# open-bldc-power.net
KiCad netlist of a schematic drawn in EAGLE
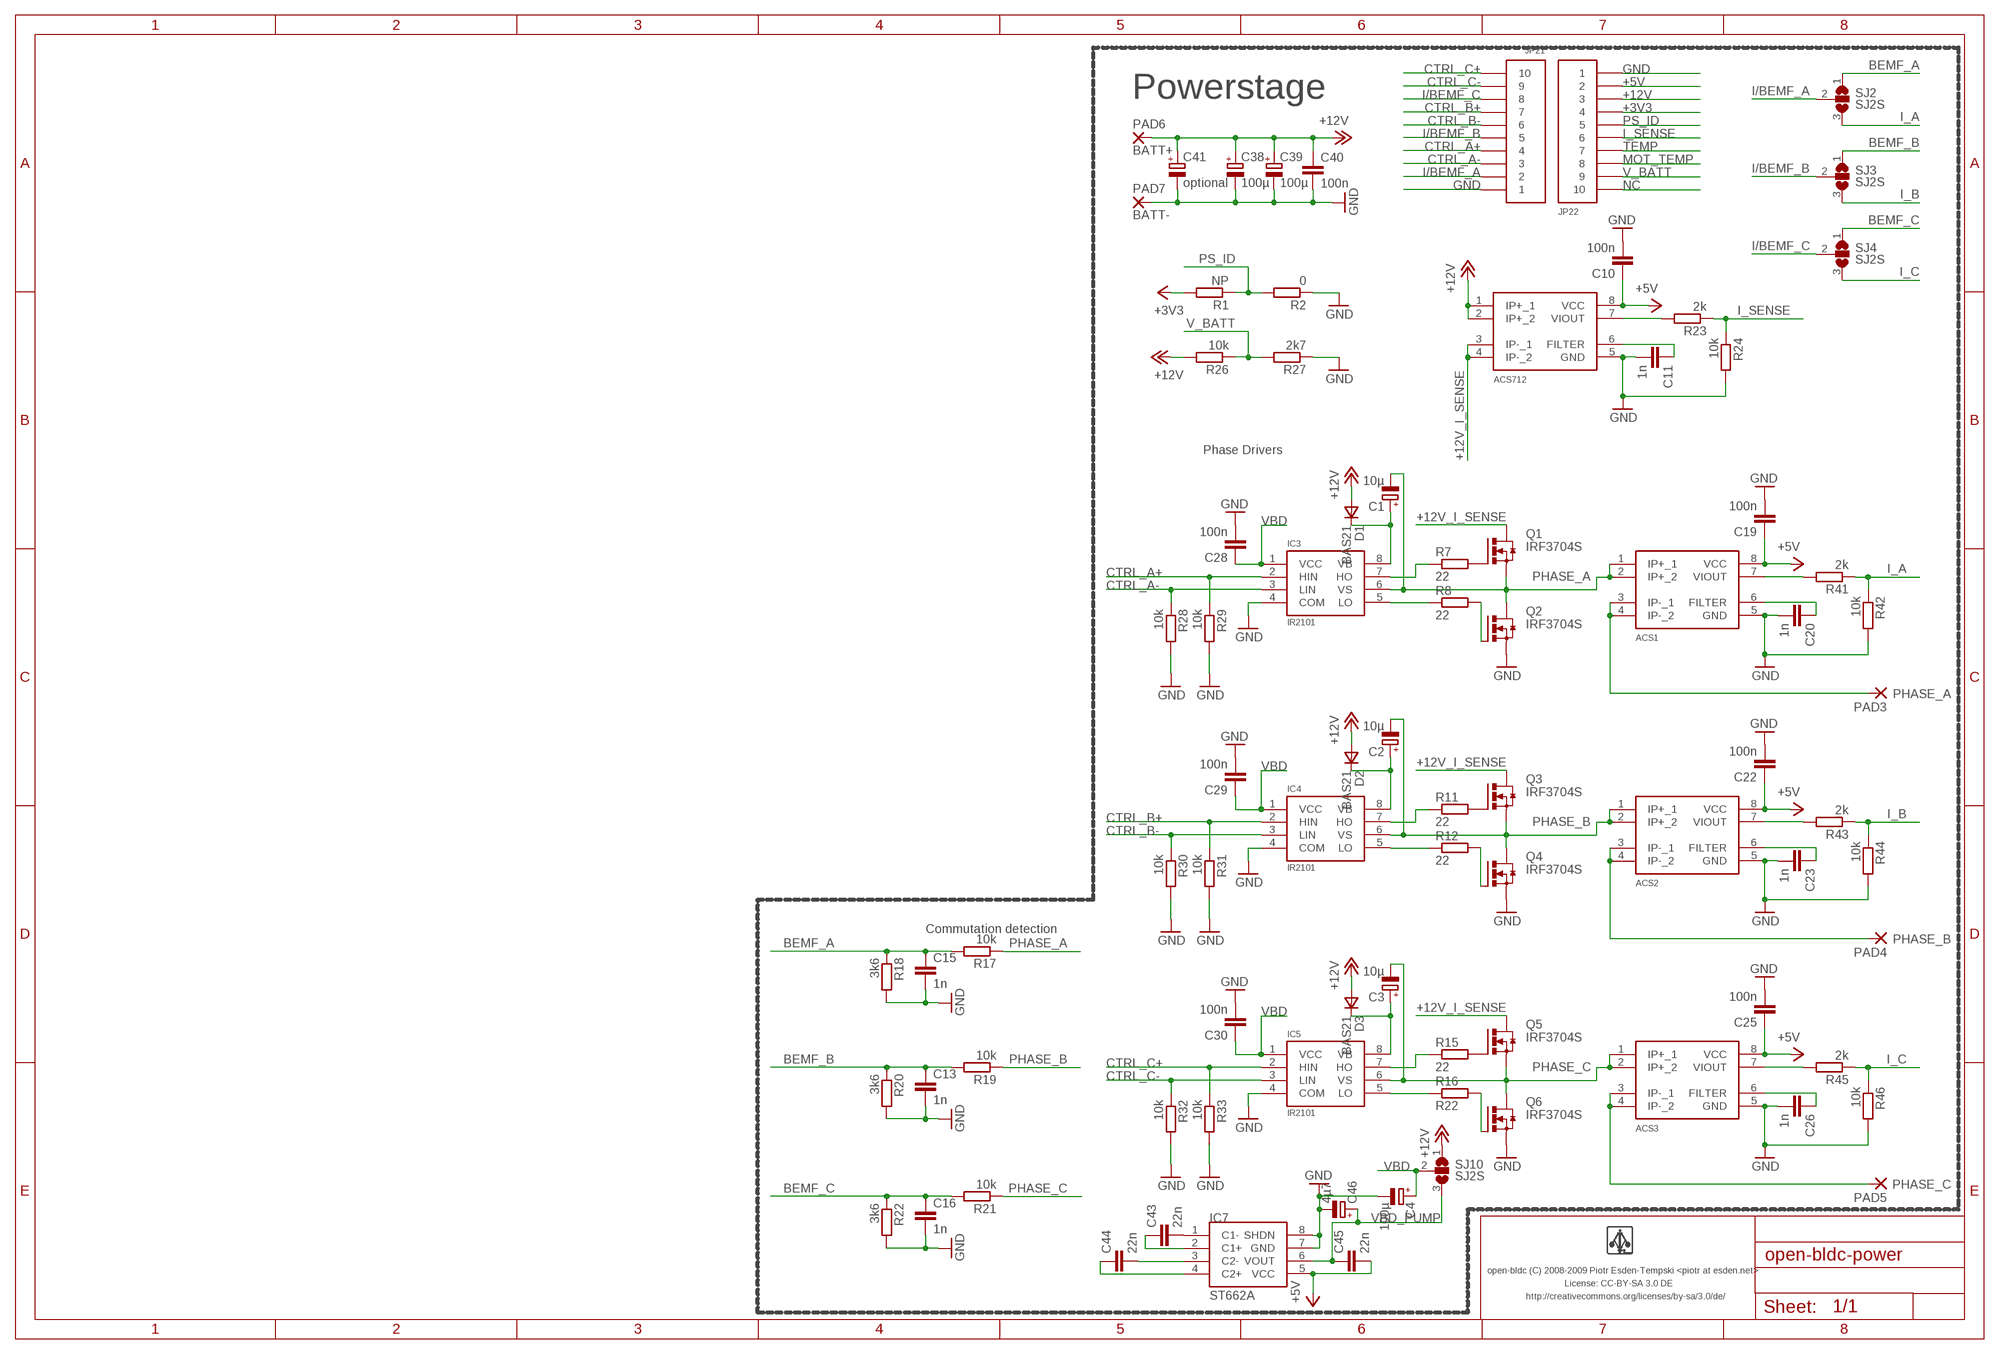
[diagram p0: schematic, sheet 1]

(export (version "E")
  (design (tool "Eeschema 10.0.6"))
  (components
    (comp (ref "ACS1")
      (value "ACS712")
      (footprint "eagle-import:SO8")
      (libsource (lib "eagle-import") (part "ACS712"))
    )
    (comp (ref "ACS2")
      (value "ACS712")
      (footprint "eagle-import:SO8")
      (libsource (lib "eagle-import") (part "ACS712"))
    )
    (comp (ref "ACS3")
      (value "ACS712")
      (footprint "eagle-import:SO8")
      (libsource (lib "eagle-import") (part "ACS712"))
    )
    (comp (ref "ACS712")
      (value "ACS712")
      (footprint "eagle-import:SO8")
      (libsource (lib "eagle-import") (part "ACS712"))
    )
    (comp (ref "C1")
      (value "10µ")
      (footprint "eagle-import:A_3216-18R")
      (libsource (lib "eagle-import") (part "CPOL-EUA/3216-18R"))
    )
    (comp (ref "C2")
      (value "10µ")
      (footprint "eagle-import:A_3216-18R")
      (libsource (lib "eagle-import") (part "CPOL-EUA/3216-18R"))
    )
    (comp (ref "C3")
      (value "10µ")
      (footprint "eagle-import:A_3216-18R")
      (libsource (lib "eagle-import") (part "CPOL-EUA/3216-18R"))
    )
    (comp (ref "C4")
      (value "100µ")
      (footprint "eagle-import:D_7343-31R")
      (libsource (lib "eagle-import") (part "CPOL-EUD/7343-31R"))
    )
    (comp (ref "C10")
      (value "100n")
      (footprint "eagle-import:C0603")
      (libsource (lib "eagle-import") (part "C-EUC0603"))
    )
    (comp (ref "C11")
      (value "1n")
      (footprint "eagle-import:C0603")
      (libsource (lib "eagle-import") (part "C-EUC0603"))
    )
    (comp (ref "C13")
      (value "1n")
      (footprint "eagle-import:C0603")
      (libsource (lib "eagle-import") (part "C-EUC0603"))
    )
    (comp (ref "C15")
      (value "1n")
      (footprint "eagle-import:C0603")
      (libsource (lib "eagle-import") (part "C-EUC0603"))
    )
    (comp (ref "C16")
      (value "1n")
      (footprint "eagle-import:C0603")
      (libsource (lib "eagle-import") (part "C-EUC0603"))
    )
    (comp (ref "C19")
      (value "100n")
      (footprint "eagle-import:C0603")
      (libsource (lib "eagle-import") (part "C-EUC0603"))
    )
    (comp (ref "C20")
      (value "1n")
      (footprint "eagle-import:C0603")
      (libsource (lib "eagle-import") (part "C-EUC0603"))
    )
    (comp (ref "C22")
      (value "100n")
      (footprint "eagle-import:C0603")
      (libsource (lib "eagle-import") (part "C-EUC0603"))
    )
    (comp (ref "C23")
      (value "1n")
      (footprint "eagle-import:C0603")
      (libsource (lib "eagle-import") (part "C-EUC0603"))
    )
    (comp (ref "C25")
      (value "100n")
      (footprint "eagle-import:C0603")
      (libsource (lib "eagle-import") (part "C-EUC0603"))
    )
    (comp (ref "C26")
      (value "1n")
      (footprint "eagle-import:C0603")
      (libsource (lib "eagle-import") (part "C-EUC0603"))
    )
    (comp (ref "C28")
      (value "100n")
      (footprint "eagle-import:C0603")
      (libsource (lib "eagle-import") (part "C-EUC0603"))
    )
    (comp (ref "C29")
      (value "100n")
      (footprint "eagle-import:C0603")
      (libsource (lib "eagle-import") (part "C-EUC0603"))
    )
    (comp (ref "C30")
      (value "100n")
      (footprint "eagle-import:C0603")
      (libsource (lib "eagle-import") (part "C-EUC0603"))
    )
    (comp (ref "C38")
      (value "100µ")
      (footprint "eagle-import:D_7343-31R")
      (libsource (lib "eagle-import") (part "CPOL-EUD/7343-31R"))
    )
    (comp (ref "C39")
      (value "100µ")
      (footprint "eagle-import:D_7343-31R")
      (libsource (lib "eagle-import") (part "CPOL-EUD/7343-31R"))
    )
    (comp (ref "C40")
      (value "100n")
      (footprint "eagle-import:C0603")
      (libsource (lib "eagle-import") (part "C-EUC0603"))
    )
    (comp (ref "C41")
      (value "optional")
      (footprint "eagle-import:E5-6")
      (libsource (lib "eagle-import") (part "CPOL-EUE5-6"))
    )
    (comp (ref "C43")
      (value "22n")
      (footprint "eagle-import:C0603")
      (libsource (lib "eagle-import") (part "C-EUC0603"))
    )
    (comp (ref "C44")
      (value "22n")
      (footprint "eagle-import:C0603")
      (libsource (lib "eagle-import") (part "C-EUC0603"))
    )
    (comp (ref "C45")
      (value "22n")
      (footprint "eagle-import:C0603")
      (libsource (lib "eagle-import") (part "C-EUC0603"))
    )
    (comp (ref "C46")
      (value "4µ7")
      (footprint "eagle-import:A_3216-18R")
      (libsource (lib "eagle-import") (part "CPOL-EUA/3216-18R"))
    )
    (comp (ref "D1")
      (value "BAS21")
      (footprint "eagle-import:SOT-23")
      (libsource (lib "eagle-import") (part "VAR2SOT23"))
    )
    (comp (ref "D2")
      (value "BAS21")
      (footprint "eagle-import:SOT-23")
      (libsource (lib "eagle-import") (part "VAR2SOT23"))
    )
    (comp (ref "D3")
      (value "BAS21")
      (footprint "eagle-import:SOT-23")
      (libsource (lib "eagle-import") (part "VAR2SOT23"))
    )
    (comp (ref "IC3")
      (value "IR2101")
      (footprint "eagle-import:SO-8")
      (libsource (lib "eagle-import") (part "IR2101"))
    )
    (comp (ref "IC4")
      (value "IR2101")
      (footprint "eagle-import:SO-8")
      (libsource (lib "eagle-import") (part "IR2101"))
    )
    (comp (ref "IC5")
      (value "IR2101")
      (footprint "eagle-import:SO-8")
      (libsource (lib "eagle-import") (part "IR2101"))
    )
    (comp (ref "IC7")
      (value "ST662A")
      (footprint "eagle-import:SO8")
      (libsource (lib "eagle-import") (part "ST662A"))
    )
    (comp (ref "JP21")
      (value "PIN_HDR_1.27MM_10")
      (footprint "eagle-import:PIN_HDR_1.27MM_10")
      (libsource (lib "eagle-import") (part "PIN_HDR_1.27MM_10_TH"))
    )
    (comp (ref "JP22")
      (value "PIN_HDR_1.27MM_10")
      (footprint "eagle-import:PIN_HDR_1.27MM_10")
      (libsource (lib "eagle-import") (part "PIN_HDR_1.27MM_10_TH"))
    )
    (comp (ref "PAD3")
      (value "PHASE_A")
      (footprint "eagle-import:SMD2,54-5,08")
      (libsource (lib "eagle-import") (part "SMD5"))
    )
    (comp (ref "PAD4")
      (value "PHASE_B")
      (footprint "eagle-import:SMD2,54-5,08")
      (libsource (lib "eagle-import") (part "SMD5"))
    )
    (comp (ref "PAD5")
      (value "PHASE_C")
      (footprint "eagle-import:SMD2,54-5,08")
      (libsource (lib "eagle-import") (part "SMD5"))
    )
    (comp (ref "PAD6")
      (value "BATT+")
      (footprint "eagle-import:SMD2,54-5,08")
      (libsource (lib "eagle-import") (part "SMD5"))
    )
    (comp (ref "PAD7")
      (value "BATT-")
      (footprint "eagle-import:SMD2,54-5,08")
      (libsource (lib "eagle-import") (part "SMD5"))
    )
    (comp (ref "Q1")
      (value "IRF3704S")
      (footprint "eagle-import:D2PACK")
      (libsource (lib "eagle-import") (part "IRF3704S"))
    )
    (comp (ref "Q2")
      (value "IRF3704S")
      (footprint "eagle-import:D2PACK")
      (libsource (lib "eagle-import") (part "IRF3704S"))
    )
    (comp (ref "Q3")
      (value "IRF3704S")
      (footprint "eagle-import:D2PACK")
      (libsource (lib "eagle-import") (part "IRF3704S"))
    )
    (comp (ref "Q4")
      (value "IRF3704S")
      (footprint "eagle-import:D2PACK")
      (libsource (lib "eagle-import") (part "IRF3704S"))
    )
    (comp (ref "Q5")
      (value "IRF3704S")
      (footprint "eagle-import:D2PACK")
      (libsource (lib "eagle-import") (part "IRF3704S"))
    )
    (comp (ref "Q6")
      (value "IRF3704S")
      (footprint "eagle-import:D2PACK")
      (libsource (lib "eagle-import") (part "IRF3704S"))
    )
    (comp (ref "R1")
      (value "NP")
      (footprint "eagle-import:R0603")
      (libsource (lib "eagle-import") (part "R-EU_R0603"))
    )
    (comp (ref "R2")
      (value "0")
      (footprint "eagle-import:R0603")
      (libsource (lib "eagle-import") (part "R-EU_R0603"))
    )
    (comp (ref "R7")
      (value "22")
      (footprint "eagle-import:R0603")
      (libsource (lib "eagle-import") (part "R-EU_R0603"))
    )
    (comp (ref "R8")
      (value "22")
      (footprint "eagle-import:R0603")
      (libsource (lib "eagle-import") (part "R-EU_R0603"))
    )
    (comp (ref "R11")
      (value "22")
      (footprint "eagle-import:R0603")
      (libsource (lib "eagle-import") (part "R-EU_R0603"))
    )
    (comp (ref "R12")
      (value "22")
      (footprint "eagle-import:R0603")
      (libsource (lib "eagle-import") (part "R-EU_R0603"))
    )
    (comp (ref "R15")
      (value "22")
      (footprint "eagle-import:R0603")
      (libsource (lib "eagle-import") (part "R-EU_R0603"))
    )
    (comp (ref "R16")
      (value "R22")
      (footprint "eagle-import:R0603")
      (libsource (lib "eagle-import") (part "R-EU_R0603"))
    )
    (comp (ref "R17")
      (value "10k")
      (footprint "eagle-import:R0603")
      (libsource (lib "eagle-import") (part "R-EU_R0603"))
    )
    (comp (ref "R18")
      (value "3k6")
      (footprint "eagle-import:R0603")
      (libsource (lib "eagle-import") (part "R-EU_R0603"))
    )
    (comp (ref "R19")
      (value "10k")
      (footprint "eagle-import:R0603")
      (libsource (lib "eagle-import") (part "R-EU_R0603"))
    )
    (comp (ref "R20")
      (value "3k6")
      (footprint "eagle-import:R0603")
      (libsource (lib "eagle-import") (part "R-EU_R0603"))
    )
    (comp (ref "R21")
      (value "10k")
      (footprint "eagle-import:R0603")
      (libsource (lib "eagle-import") (part "R-EU_R0603"))
    )
    (comp (ref "R22")
      (value "3k6")
      (footprint "eagle-import:R0603")
      (libsource (lib "eagle-import") (part "R-EU_R0603"))
    )
    (comp (ref "R23")
      (value "2k")
      (footprint "eagle-import:R0603")
      (libsource (lib "eagle-import") (part "R-EU_R0603"))
    )
    (comp (ref "R24")
      (value "10k")
      (footprint "eagle-import:R0603")
      (libsource (lib "eagle-import") (part "R-EU_R0603"))
    )
    (comp (ref "R26")
      (value "10k")
      (footprint "eagle-import:R0603")
      (libsource (lib "eagle-import") (part "R-EU_R0603"))
    )
    (comp (ref "R27")
      (value "2k7")
      (footprint "eagle-import:R0603")
      (libsource (lib "eagle-import") (part "R-EU_R0603"))
    )
    (comp (ref "R28")
      (value "10k")
      (footprint "eagle-import:R0603")
      (libsource (lib "eagle-import") (part "R-EU_R0603"))
    )
    (comp (ref "R29")
      (value "10k")
      (footprint "eagle-import:R0603")
      (libsource (lib "eagle-import") (part "R-EU_R0603"))
    )
    (comp (ref "R30")
      (value "10k")
      (footprint "eagle-import:R0603")
      (libsource (lib "eagle-import") (part "R-EU_R0603"))
    )
    (comp (ref "R31")
      (value "10k")
      (footprint "eagle-import:R0603")
      (libsource (lib "eagle-import") (part "R-EU_R0603"))
    )
    (comp (ref "R32")
      (value "10k")
      (footprint "eagle-import:R0603")
      (libsource (lib "eagle-import") (part "R-EU_R0603"))
    )
    (comp (ref "R33")
      (value "10k")
      (footprint "eagle-import:R0603")
      (libsource (lib "eagle-import") (part "R-EU_R0603"))
    )
    (comp (ref "R41")
      (value "2k")
      (footprint "eagle-import:R0603")
      (libsource (lib "eagle-import") (part "R-EU_R0603"))
    )
    (comp (ref "R42")
      (value "10k")
      (footprint "eagle-import:R0603")
      (libsource (lib "eagle-import") (part "R-EU_R0603"))
    )
    (comp (ref "R43")
      (value "2k")
      (footprint "eagle-import:R0603")
      (libsource (lib "eagle-import") (part "R-EU_R0603"))
    )
    (comp (ref "R44")
      (value "10k")
      (footprint "eagle-import:R0603")
      (libsource (lib "eagle-import") (part "R-EU_R0603"))
    )
    (comp (ref "R45")
      (value "2k")
      (footprint "eagle-import:R0603")
      (libsource (lib "eagle-import") (part "R-EU_R0603"))
    )
    (comp (ref "R46")
      (value "10k")
      (footprint "eagle-import:R0603")
      (libsource (lib "eagle-import") (part "R-EU_R0603"))
    )
    (comp (ref "SJ2")
      (value "SJ2S")
      (footprint "eagle-import:SJ2S")
      (libsource (lib "eagle-import") (part "SJ2S"))
    )
    (comp (ref "SJ3")
      (value "SJ2S")
      (footprint "eagle-import:SJ2S")
      (libsource (lib "eagle-import") (part "SJ2S"))
    )
    (comp (ref "SJ4")
      (value "SJ2S")
      (footprint "eagle-import:SJ2S")
      (libsource (lib "eagle-import") (part "SJ2S"))
    )
    (comp (ref "SJ10")
      (value "SJ2S")
      (footprint "eagle-import:SJ2S")
      (libsource (lib "eagle-import") (part "SJ2S"))
    )
  )
  (nets
    (net (code "1") (name "+3V3") (class "Default")
      (node (ref "JP22") (pin "P$4") (pinfunction "4_P$4") (pintype "bidirectional"))
      (node (ref "R1") (pin "2") (pinfunction "2_2") (pintype "passive"))
    )
    (net (code "2") (name "+5V") (class "Default")
      (node (ref "ACS1") (pin "8") (pinfunction "VCC_8") (pintype "bidirectional"))
      (node (ref "ACS2") (pin "8") (pinfunction "VCC_8") (pintype "bidirectional"))
      (node (ref "ACS3") (pin "8") (pinfunction "VCC_8") (pintype "bidirectional"))
      (node (ref "ACS712") (pin "8") (pinfunction "VCC_8") (pintype "bidirectional"))
      (node (ref "C10") (pin "1") (pinfunction "1_1") (pintype "passive"))
      (node (ref "C19") (pin "1") (pinfunction "1_1") (pintype "passive"))
      (node (ref "C22") (pin "1") (pinfunction "1_1") (pintype "passive"))
      (node (ref "C25") (pin "1") (pinfunction "1_1") (pintype "passive"))
      (node (ref "C45") (pin "2") (pinfunction "2_2") (pintype "passive"))
      (node (ref "IC7") (pin "5") (pinfunction "VCC_5") (pintype "bidirectional"))
      (node (ref "JP22") (pin "P$2") (pinfunction "2_P$2") (pintype "bidirectional"))
    )
    (net (code "3") (name "+12V") (class "Default")
      (node (ref "ACS712") (pin "1") (pinfunction "IP+_1_1") (pintype "bidirectional"))
      (node (ref "ACS712") (pin "2") (pinfunction "IP+_2_2") (pintype "bidirectional"))
      (node (ref "C38") (pin "+") (pinfunction "+_+") (pintype "passive"))
      (node (ref "C39") (pin "+") (pinfunction "+_+") (pintype "passive"))
      (node (ref "C40") (pin "1") (pinfunction "1_1") (pintype "passive"))
      (node (ref "C41") (pin "+") (pinfunction "+_+") (pintype "passive"))
      (node (ref "D1") (pin "3") (pinfunction "A_3") (pintype "passive"))
      (node (ref "D2") (pin "3") (pinfunction "A_3") (pintype "passive"))
      (node (ref "D3") (pin "3") (pinfunction "A_3") (pintype "passive"))
      (node (ref "JP22") (pin "P$3") (pinfunction "3_P$3") (pintype "bidirectional"))
      (node (ref "PAD6") (pin "1") (pinfunction "P_1") (pintype "passive"))
      (node (ref "R26") (pin "2") (pinfunction "2_2") (pintype "passive"))
      (node (ref "SJ10") (pin "1") (pinfunction "1_1") (pintype "passive"))
    )
    (net (code "4") (name "/+12V_I_SENSE") (class "Default")
      (node (ref "ACS712") (pin "3") (pinfunction "IP-_1_3") (pintype "bidirectional"))
      (node (ref "ACS712") (pin "4") (pinfunction "IP-_2_4") (pintype "bidirectional"))
      (node (ref "Q1") (pin "2") (pinfunction "D_2") (pintype "passive"))
      (node (ref "Q3") (pin "2") (pinfunction "D_2") (pintype "passive"))
      (node (ref "Q5") (pin "2") (pinfunction "D_2") (pintype "passive"))
    )
    (net (code "5") (name "/BEMF_A") (class "Default")
      (node (ref "C15") (pin "1") (pinfunction "1_1") (pintype "passive"))
      (node (ref "R17") (pin "2") (pinfunction "2_2") (pintype "passive"))
      (node (ref "R18") (pin "1") (pinfunction "1_1") (pintype "passive"))
      (node (ref "SJ2") (pin "1") (pinfunction "1_1") (pintype "passive"))
    )
    (net (code "6") (name "/BEMF_B") (class "Default")
      (node (ref "C13") (pin "1") (pinfunction "1_1") (pintype "passive"))
      (node (ref "R19") (pin "2") (pinfunction "2_2") (pintype "passive"))
      (node (ref "R20") (pin "1") (pinfunction "1_1") (pintype "passive"))
      (node (ref "SJ3") (pin "1") (pinfunction "1_1") (pintype "passive"))
    )
    (net (code "7") (name "/BEMF_C") (class "Default")
      (node (ref "C16") (pin "1") (pinfunction "1_1") (pintype "passive"))
      (node (ref "R21") (pin "2") (pinfunction "2_2") (pintype "passive"))
      (node (ref "R22") (pin "1") (pinfunction "1_1") (pintype "passive"))
      (node (ref "SJ4") (pin "1") (pinfunction "1_1") (pintype "passive"))
    )
    (net (code "8") (name "/CTRL_A+") (class "Default")
      (node (ref "IC3") (pin "2") (pinfunction "HIN_2") (pintype "bidirectional"))
      (node (ref "JP21") (pin "P$4") (pinfunction "4_P$4") (pintype "bidirectional"))
      (node (ref "R29") (pin "1") (pinfunction "1_1") (pintype "passive"))
    )
    (net (code "9") (name "/CTRL_A-") (class "Default")
      (node (ref "IC3") (pin "3") (pinfunction "LIN_3") (pintype "bidirectional"))
      (node (ref "JP21") (pin "P$3") (pinfunction "3_P$3") (pintype "bidirectional"))
      (node (ref "R28") (pin "1") (pinfunction "1_1") (pintype "passive"))
    )
    (net (code "10") (name "/CTRL_B+") (class "Default")
      (node (ref "IC4") (pin "2") (pinfunction "HIN_2") (pintype "bidirectional"))
      (node (ref "JP21") (pin "P$7") (pinfunction "7_P$7") (pintype "bidirectional"))
      (node (ref "R31") (pin "1") (pinfunction "1_1") (pintype "passive"))
    )
    (net (code "11") (name "/CTRL_B-") (class "Default")
      (node (ref "IC4") (pin "3") (pinfunction "LIN_3") (pintype "bidirectional"))
      (node (ref "JP21") (pin "P$6") (pinfunction "6_P$6") (pintype "bidirectional"))
      (node (ref "R30") (pin "1") (pinfunction "1_1") (pintype "passive"))
    )
    (net (code "12") (name "/CTRL_C+") (class "Default")
      (node (ref "IC5") (pin "2") (pinfunction "HIN_2") (pintype "bidirectional"))
      (node (ref "JP21") (pin "P$10") (pinfunction "10_P$10") (pintype "bidirectional"))
      (node (ref "R33") (pin "1") (pinfunction "1_1") (pintype "passive"))
    )
    (net (code "13") (name "/CTRL_C-") (class "Default")
      (node (ref "IC5") (pin "3") (pinfunction "LIN_3") (pintype "bidirectional"))
      (node (ref "JP21") (pin "P$9") (pinfunction "9_P$9") (pintype "bidirectional"))
      (node (ref "R32") (pin "1") (pinfunction "1_1") (pintype "passive"))
    )
    (net (code "14") (name "/I_A") (class "Default")
      (node (ref "R41") (pin "1") (pinfunction "1_1") (pintype "passive"))
      (node (ref "R42") (pin "1") (pinfunction "1_1") (pintype "passive"))
      (node (ref "SJ2") (pin "3") (pinfunction "3_3") (pintype "passive"))
    )
    (net (code "15") (name "/I_B") (class "Default")
      (node (ref "R43") (pin "1") (pinfunction "1_1") (pintype "passive"))
      (node (ref "R44") (pin "1") (pinfunction "1_1") (pintype "passive"))
      (node (ref "SJ3") (pin "3") (pinfunction "3_3") (pintype "passive"))
    )
    (net (code "16") (name "/I_C") (class "Default")
      (node (ref "R45") (pin "1") (pinfunction "1_1") (pintype "passive"))
      (node (ref "R46") (pin "1") (pinfunction "1_1") (pintype "passive"))
      (node (ref "SJ4") (pin "3") (pinfunction "3_3") (pintype "passive"))
    )
    (net (code "17") (name "/I_SENSE") (class "Default")
      (node (ref "JP22") (pin "P$6") (pinfunction "6_P$6") (pintype "bidirectional"))
      (node (ref "R23") (pin "1") (pinfunction "1_1") (pintype "passive"))
      (node (ref "R24") (pin "1") (pinfunction "1_1") (pintype "passive"))
    )
    (net (code "18") (name "/I{slash}BEMF_A") (class "Default")
      (node (ref "JP21") (pin "P$2") (pinfunction "2_P$2") (pintype "bidirectional"))
      (node (ref "SJ2") (pin "2") (pinfunction "2_2") (pintype "passive"))
    )
    (net (code "19") (name "/I{slash}BEMF_B") (class "Default")
      (node (ref "JP21") (pin "P$5") (pinfunction "5_P$5") (pintype "bidirectional"))
      (node (ref "SJ3") (pin "2") (pinfunction "2_2") (pintype "passive"))
    )
    (net (code "20") (name "/I{slash}BEMF_C") (class "Default")
      (node (ref "JP21") (pin "P$8") (pinfunction "8_P$8") (pintype "bidirectional"))
      (node (ref "SJ4") (pin "2") (pinfunction "2_2") (pintype "passive"))
    )
    (net (code "21") (name "/MOT_TEMP") (class "Default")
      (node (ref "JP22") (pin "P$8") (pinfunction "8_P$8") (pintype "bidirectional"))
    )
    (net (code "22") (name "/NC") (class "Default")
      (node (ref "JP22") (pin "P$10") (pinfunction "10_P$10") (pintype "bidirectional"))
    )
    (net (code "23") (name "/PHASE_A") (class "Default")
      (node (ref "ACS1") (pin "1") (pinfunction "IP+_1_1") (pintype "bidirectional"))
      (node (ref "ACS1") (pin "2") (pinfunction "IP+_2_2") (pintype "bidirectional"))
      (node (ref "C1") (pin "-") (pinfunction "-_-") (pintype "passive"))
      (node (ref "IC3") (pin "6") (pinfunction "VS_6") (pintype "bidirectional"))
      (node (ref "Q1") (pin "3") (pinfunction "S_3") (pintype "passive"))
      (node (ref "Q2") (pin "2") (pinfunction "D_2") (pintype "passive"))
      (node (ref "R17") (pin "1") (pinfunction "1_1") (pintype "passive"))
    )
    (net (code "24") (name "/PHASE_B") (class "Default")
      (node (ref "ACS2") (pin "1") (pinfunction "IP+_1_1") (pintype "bidirectional"))
      (node (ref "ACS2") (pin "2") (pinfunction "IP+_2_2") (pintype "bidirectional"))
      (node (ref "C2") (pin "-") (pinfunction "-_-") (pintype "passive"))
      (node (ref "IC4") (pin "6") (pinfunction "VS_6") (pintype "bidirectional"))
      (node (ref "Q3") (pin "3") (pinfunction "S_3") (pintype "passive"))
      (node (ref "Q4") (pin "2") (pinfunction "D_2") (pintype "passive"))
      (node (ref "R19") (pin "1") (pinfunction "1_1") (pintype "passive"))
    )
    (net (code "25") (name "/PHASE_C") (class "Default")
      (node (ref "ACS3") (pin "1") (pinfunction "IP+_1_1") (pintype "bidirectional"))
      (node (ref "ACS3") (pin "2") (pinfunction "IP+_2_2") (pintype "bidirectional"))
      (node (ref "C3") (pin "-") (pinfunction "-_-") (pintype "passive"))
      (node (ref "IC5") (pin "6") (pinfunction "VS_6") (pintype "bidirectional"))
      (node (ref "Q5") (pin "3") (pinfunction "S_3") (pintype "passive"))
      (node (ref "Q6") (pin "2") (pinfunction "D_2") (pintype "passive"))
      (node (ref "R21") (pin "1") (pinfunction "1_1") (pintype "passive"))
    )
    (net (code "26") (name "/PS_ID") (class "Default")
      (node (ref "JP22") (pin "P$5") (pinfunction "5_P$5") (pintype "bidirectional"))
      (node (ref "R1") (pin "1") (pinfunction "1_1") (pintype "passive"))
      (node (ref "R2") (pin "2") (pinfunction "2_2") (pintype "passive"))
    )
    (net (code "27") (name "/TEMP") (class "Default")
      (node (ref "JP22") (pin "P$7") (pinfunction "7_P$7") (pintype "bidirectional"))
    )
    (net (code "28") (name "/VBD") (class "Default")
      (node (ref "C28") (pin "1") (pinfunction "1_1") (pintype "passive"))
      (node (ref "C29") (pin "1") (pinfunction "1_1") (pintype "passive"))
      (node (ref "C30") (pin "1") (pinfunction "1_1") (pintype "passive"))
      (node (ref "C4") (pin "+") (pinfunction "+_+") (pintype "passive"))
      (node (ref "IC3") (pin "1") (pinfunction "VCC_1") (pintype "bidirectional"))
      (node (ref "IC4") (pin "1") (pinfunction "VCC_1") (pintype "bidirectional"))
      (node (ref "IC5") (pin "1") (pinfunction "VCC_1") (pintype "bidirectional"))
      (node (ref "SJ10") (pin "2") (pinfunction "2_2") (pintype "passive"))
    )
    (net (code "29") (name "/VBD_PUMP") (class "Default")
      (node (ref "C45") (pin "1") (pinfunction "1_1") (pintype "passive"))
      (node (ref "C46") (pin "+") (pinfunction "+_+") (pintype "passive"))
      (node (ref "IC7") (pin "6") (pinfunction "VOUT_6") (pintype "bidirectional"))
      (node (ref "SJ10") (pin "3") (pinfunction "3_3") (pintype "passive"))
    )
    (net (code "30") (name "/V_BATT") (class "Default")
      (node (ref "JP22") (pin "P$9") (pinfunction "9_P$9") (pintype "bidirectional"))
      (node (ref "R26") (pin "1") (pinfunction "1_1") (pintype "passive"))
      (node (ref "R27") (pin "2") (pinfunction "2_2") (pintype "passive"))
    )
    (net (code "31") (name "GND") (class "Default")
      (node (ref "ACS1") (pin "5") (pinfunction "GND_5") (pintype "bidirectional"))
      (node (ref "ACS2") (pin "5") (pinfunction "GND_5") (pintype "bidirectional"))
      (node (ref "ACS3") (pin "5") (pinfunction "GND_5") (pintype "bidirectional"))
      (node (ref "ACS712") (pin "5") (pinfunction "GND_5") (pintype "bidirectional"))
      (node (ref "C10") (pin "2") (pinfunction "2_2") (pintype "passive"))
      (node (ref "C11") (pin "2") (pinfunction "2_2") (pintype "passive"))
      (node (ref "C13") (pin "2") (pinfunction "2_2") (pintype "passive"))
      (node (ref "C15") (pin "2") (pinfunction "2_2") (pintype "passive"))
      (node (ref "C16") (pin "2") (pinfunction "2_2") (pintype "passive"))
      (node (ref "C19") (pin "2") (pinfunction "2_2") (pintype "passive"))
      (node (ref "C20") (pin "2") (pinfunction "2_2") (pintype "passive"))
      (node (ref "C22") (pin "2") (pinfunction "2_2") (pintype "passive"))
      (node (ref "C23") (pin "2") (pinfunction "2_2") (pintype "passive"))
      (node (ref "C25") (pin "2") (pinfunction "2_2") (pintype "passive"))
      (node (ref "C26") (pin "2") (pinfunction "2_2") (pintype "passive"))
      (node (ref "C28") (pin "2") (pinfunction "2_2") (pintype "passive"))
      (node (ref "C29") (pin "2") (pinfunction "2_2") (pintype "passive"))
      (node (ref "C30") (pin "2") (pinfunction "2_2") (pintype "passive"))
      (node (ref "C38") (pin "-") (pinfunction "-_-") (pintype "passive"))
      (node (ref "C39") (pin "-") (pinfunction "-_-") (pintype "passive"))
      (node (ref "C4") (pin "-") (pinfunction "-_-") (pintype "passive"))
      (node (ref "C40") (pin "2") (pinfunction "2_2") (pintype "passive"))
      (node (ref "C41") (pin "-") (pinfunction "-_-") (pintype "passive"))
      (node (ref "C46") (pin "-") (pinfunction "-_-") (pintype "passive"))
      (node (ref "IC3") (pin "4") (pinfunction "COM_4") (pintype "bidirectional"))
      (node (ref "IC4") (pin "4") (pinfunction "COM_4") (pintype "bidirectional"))
      (node (ref "IC5") (pin "4") (pinfunction "COM_4") (pintype "bidirectional"))
      (node (ref "IC7") (pin "7") (pinfunction "GND_7") (pintype "bidirectional"))
      (node (ref "IC7") (pin "8") (pinfunction "SHDN_8") (pintype "bidirectional"))
      (node (ref "JP21") (pin "P$1") (pinfunction "1_P$1") (pintype "bidirectional"))
      (node (ref "JP22") (pin "P$1") (pinfunction "1_P$1") (pintype "bidirectional"))
      (node (ref "PAD7") (pin "1") (pinfunction "P_1") (pintype "passive"))
      (node (ref "Q2") (pin "3") (pinfunction "S_3") (pintype "passive"))
      (node (ref "Q4") (pin "3") (pinfunction "S_3") (pintype "passive"))
      (node (ref "Q6") (pin "3") (pinfunction "S_3") (pintype "passive"))
      (node (ref "R18") (pin "2") (pinfunction "2_2") (pintype "passive"))
      (node (ref "R2") (pin "1") (pinfunction "1_1") (pintype "passive"))
      (node (ref "R20") (pin "2") (pinfunction "2_2") (pintype "passive"))
      (node (ref "R22") (pin "2") (pinfunction "2_2") (pintype "passive"))
      (node (ref "R24") (pin "2") (pinfunction "2_2") (pintype "passive"))
      (node (ref "R27") (pin "1") (pinfunction "1_1") (pintype "passive"))
      (node (ref "R28") (pin "2") (pinfunction "2_2") (pintype "passive"))
      (node (ref "R29") (pin "2") (pinfunction "2_2") (pintype "passive"))
      (node (ref "R30") (pin "2") (pinfunction "2_2") (pintype "passive"))
      (node (ref "R31") (pin "2") (pinfunction "2_2") (pintype "passive"))
      (node (ref "R32") (pin "2") (pinfunction "2_2") (pintype "passive"))
      (node (ref "R33") (pin "2") (pinfunction "2_2") (pintype "passive"))
      (node (ref "R42") (pin "2") (pinfunction "2_2") (pintype "passive"))
      (node (ref "R44") (pin "2") (pinfunction "2_2") (pintype "passive"))
      (node (ref "R46") (pin "2") (pinfunction "2_2") (pintype "passive"))
    )
    (net (code "32") (name "Net-(ACS1-FILTER)") (class "Default")
      (node (ref "ACS1") (pin "6") (pinfunction "FILTER_6") (pintype "bidirectional"))
      (node (ref "C20") (pin "1") (pinfunction "1_1") (pintype "passive"))
    )
    (net (code "33") (name "Net-(ACS1-IP-_1)") (class "Default")
      (node (ref "ACS1") (pin "3") (pinfunction "IP-_1_3") (pintype "bidirectional"))
      (node (ref "ACS1") (pin "4") (pinfunction "IP-_2_4") (pintype "bidirectional"))
      (node (ref "PAD3") (pin "1") (pinfunction "P_1") (pintype "passive"))
    )
    (net (code "34") (name "Net-(ACS1-VIOUT)") (class "Default")
      (node (ref "ACS1") (pin "7") (pinfunction "VIOUT_7") (pintype "bidirectional"))
      (node (ref "R41") (pin "2") (pinfunction "2_2") (pintype "passive"))
    )
    (net (code "35") (name "Net-(ACS2-FILTER)") (class "Default")
      (node (ref "ACS2") (pin "6") (pinfunction "FILTER_6") (pintype "bidirectional"))
      (node (ref "C23") (pin "1") (pinfunction "1_1") (pintype "passive"))
    )
    (net (code "36") (name "Net-(ACS2-IP-_1)") (class "Default")
      (node (ref "ACS2") (pin "3") (pinfunction "IP-_1_3") (pintype "bidirectional"))
      (node (ref "ACS2") (pin "4") (pinfunction "IP-_2_4") (pintype "bidirectional"))
      (node (ref "PAD4") (pin "1") (pinfunction "P_1") (pintype "passive"))
    )
    (net (code "37") (name "Net-(ACS2-VIOUT)") (class "Default")
      (node (ref "ACS2") (pin "7") (pinfunction "VIOUT_7") (pintype "bidirectional"))
      (node (ref "R43") (pin "2") (pinfunction "2_2") (pintype "passive"))
    )
    (net (code "38") (name "Net-(ACS3-FILTER)") (class "Default")
      (node (ref "ACS3") (pin "6") (pinfunction "FILTER_6") (pintype "bidirectional"))
      (node (ref "C26") (pin "1") (pinfunction "1_1") (pintype "passive"))
    )
    (net (code "39") (name "Net-(ACS3-IP-_1)") (class "Default")
      (node (ref "ACS3") (pin "3") (pinfunction "IP-_1_3") (pintype "bidirectional"))
      (node (ref "ACS3") (pin "4") (pinfunction "IP-_2_4") (pintype "bidirectional"))
      (node (ref "PAD5") (pin "1") (pinfunction "P_1") (pintype "passive"))
    )
    (net (code "40") (name "Net-(ACS3-VIOUT)") (class "Default")
      (node (ref "ACS3") (pin "7") (pinfunction "VIOUT_7") (pintype "bidirectional"))
      (node (ref "R45") (pin "2") (pinfunction "2_2") (pintype "passive"))
    )
    (net (code "41") (name "Net-(ACS712-FILTER)") (class "Default")
      (node (ref "ACS712") (pin "6") (pinfunction "FILTER_6") (pintype "bidirectional"))
      (node (ref "C11") (pin "1") (pinfunction "1_1") (pintype "passive"))
    )
    (net (code "42") (name "Net-(ACS712-VIOUT)") (class "Default")
      (node (ref "ACS712") (pin "7") (pinfunction "VIOUT_7") (pintype "bidirectional"))
      (node (ref "R23") (pin "2") (pinfunction "2_2") (pintype "passive"))
    )
    (net (code "43") (name "Net-(D1-C)") (class "Default")
      (node (ref "C1") (pin "+") (pinfunction "+_+") (pintype "passive"))
      (node (ref "D1") (pin "1") (pinfunction "C_1") (pintype "passive"))
      (node (ref "IC3") (pin "8") (pinfunction "VB_8") (pintype "bidirectional"))
    )
    (net (code "44") (name "Net-(D2-C)") (class "Default")
      (node (ref "C2") (pin "+") (pinfunction "+_+") (pintype "passive"))
      (node (ref "D2") (pin "1") (pinfunction "C_1") (pintype "passive"))
      (node (ref "IC4") (pin "8") (pinfunction "VB_8") (pintype "bidirectional"))
    )
    (net (code "45") (name "Net-(D3-C)") (class "Default")
      (node (ref "C3") (pin "+") (pinfunction "+_+") (pintype "passive"))
      (node (ref "D3") (pin "1") (pinfunction "C_1") (pintype "passive"))
      (node (ref "IC5") (pin "8") (pinfunction "VB_8") (pintype "bidirectional"))
    )
    (net (code "46") (name "Net-(IC3-HO)") (class "Default")
      (node (ref "IC3") (pin "7") (pinfunction "HO_7") (pintype "bidirectional"))
      (node (ref "R7") (pin "1") (pinfunction "1_1") (pintype "passive"))
    )
    (net (code "47") (name "Net-(IC3-LO)") (class "Default")
      (node (ref "IC3") (pin "5") (pinfunction "LO_5") (pintype "bidirectional"))
      (node (ref "R8") (pin "1") (pinfunction "1_1") (pintype "passive"))
    )
    (net (code "48") (name "Net-(IC4-HO)") (class "Default")
      (node (ref "IC4") (pin "7") (pinfunction "HO_7") (pintype "bidirectional"))
      (node (ref "R11") (pin "1") (pinfunction "1_1") (pintype "passive"))
    )
    (net (code "49") (name "Net-(IC4-LO)") (class "Default")
      (node (ref "IC4") (pin "5") (pinfunction "LO_5") (pintype "bidirectional"))
      (node (ref "R12") (pin "1") (pinfunction "1_1") (pintype "passive"))
    )
    (net (code "50") (name "Net-(IC5-HO)") (class "Default")
      (node (ref "IC5") (pin "7") (pinfunction "HO_7") (pintype "bidirectional"))
      (node (ref "R15") (pin "1") (pinfunction "1_1") (pintype "passive"))
    )
    (net (code "51") (name "Net-(IC5-LO)") (class "Default")
      (node (ref "IC5") (pin "5") (pinfunction "LO_5") (pintype "bidirectional"))
      (node (ref "R16") (pin "1") (pinfunction "1_1") (pintype "passive"))
    )
    (net (code "52") (name "Net-(IC7-C1+)") (class "Default")
      (node (ref "C43") (pin "1") (pinfunction "1_1") (pintype "passive"))
      (node (ref "IC7") (pin "2") (pinfunction "C1+_2") (pintype "bidirectional"))
    )
    (net (code "53") (name "Net-(IC7-C1-)") (class "Default")
      (node (ref "C43") (pin "2") (pinfunction "2_2") (pintype "passive"))
      (node (ref "IC7") (pin "1") (pinfunction "C1-_1") (pintype "bidirectional"))
    )
    (net (code "54") (name "Net-(IC7-C2+)") (class "Default")
      (node (ref "C44") (pin "1") (pinfunction "1_1") (pintype "passive"))
      (node (ref "IC7") (pin "4") (pinfunction "C2+_4") (pintype "bidirectional"))
    )
    (net (code "55") (name "Net-(IC7-C2-)") (class "Default")
      (node (ref "C44") (pin "2") (pinfunction "2_2") (pintype "passive"))
      (node (ref "IC7") (pin "3") (pinfunction "C2-_3") (pintype "bidirectional"))
    )
    (net (code "56") (name "Net-(Q1-G)") (class "Default")
      (node (ref "Q1") (pin "1") (pinfunction "G_1") (pintype "passive"))
      (node (ref "R7") (pin "2") (pinfunction "2_2") (pintype "passive"))
    )
    (net (code "57") (name "Net-(Q2-G)") (class "Default")
      (node (ref "Q2") (pin "1") (pinfunction "G_1") (pintype "passive"))
      (node (ref "R8") (pin "2") (pinfunction "2_2") (pintype "passive"))
    )
    (net (code "58") (name "Net-(Q3-G)") (class "Default")
      (node (ref "Q3") (pin "1") (pinfunction "G_1") (pintype "passive"))
      (node (ref "R11") (pin "2") (pinfunction "2_2") (pintype "passive"))
    )
    (net (code "59") (name "Net-(Q4-G)") (class "Default")
      (node (ref "Q4") (pin "1") (pinfunction "G_1") (pintype "passive"))
      (node (ref "R12") (pin "2") (pinfunction "2_2") (pintype "passive"))
    )
    (net (code "60") (name "Net-(Q5-G)") (class "Default")
      (node (ref "Q5") (pin "1") (pinfunction "G_1") (pintype "passive"))
      (node (ref "R15") (pin "2") (pinfunction "2_2") (pintype "passive"))
    )
    (net (code "61") (name "Net-(Q6-G)") (class "Default")
      (node (ref "Q6") (pin "1") (pinfunction "G_1") (pintype "passive"))
      (node (ref "R16") (pin "2") (pinfunction "2_2") (pintype "passive"))
    )
  )
)
